# SCH_Hacker-Card_2024-10-03.net
KiCad netlist of a schematic drawn in EasyEDA
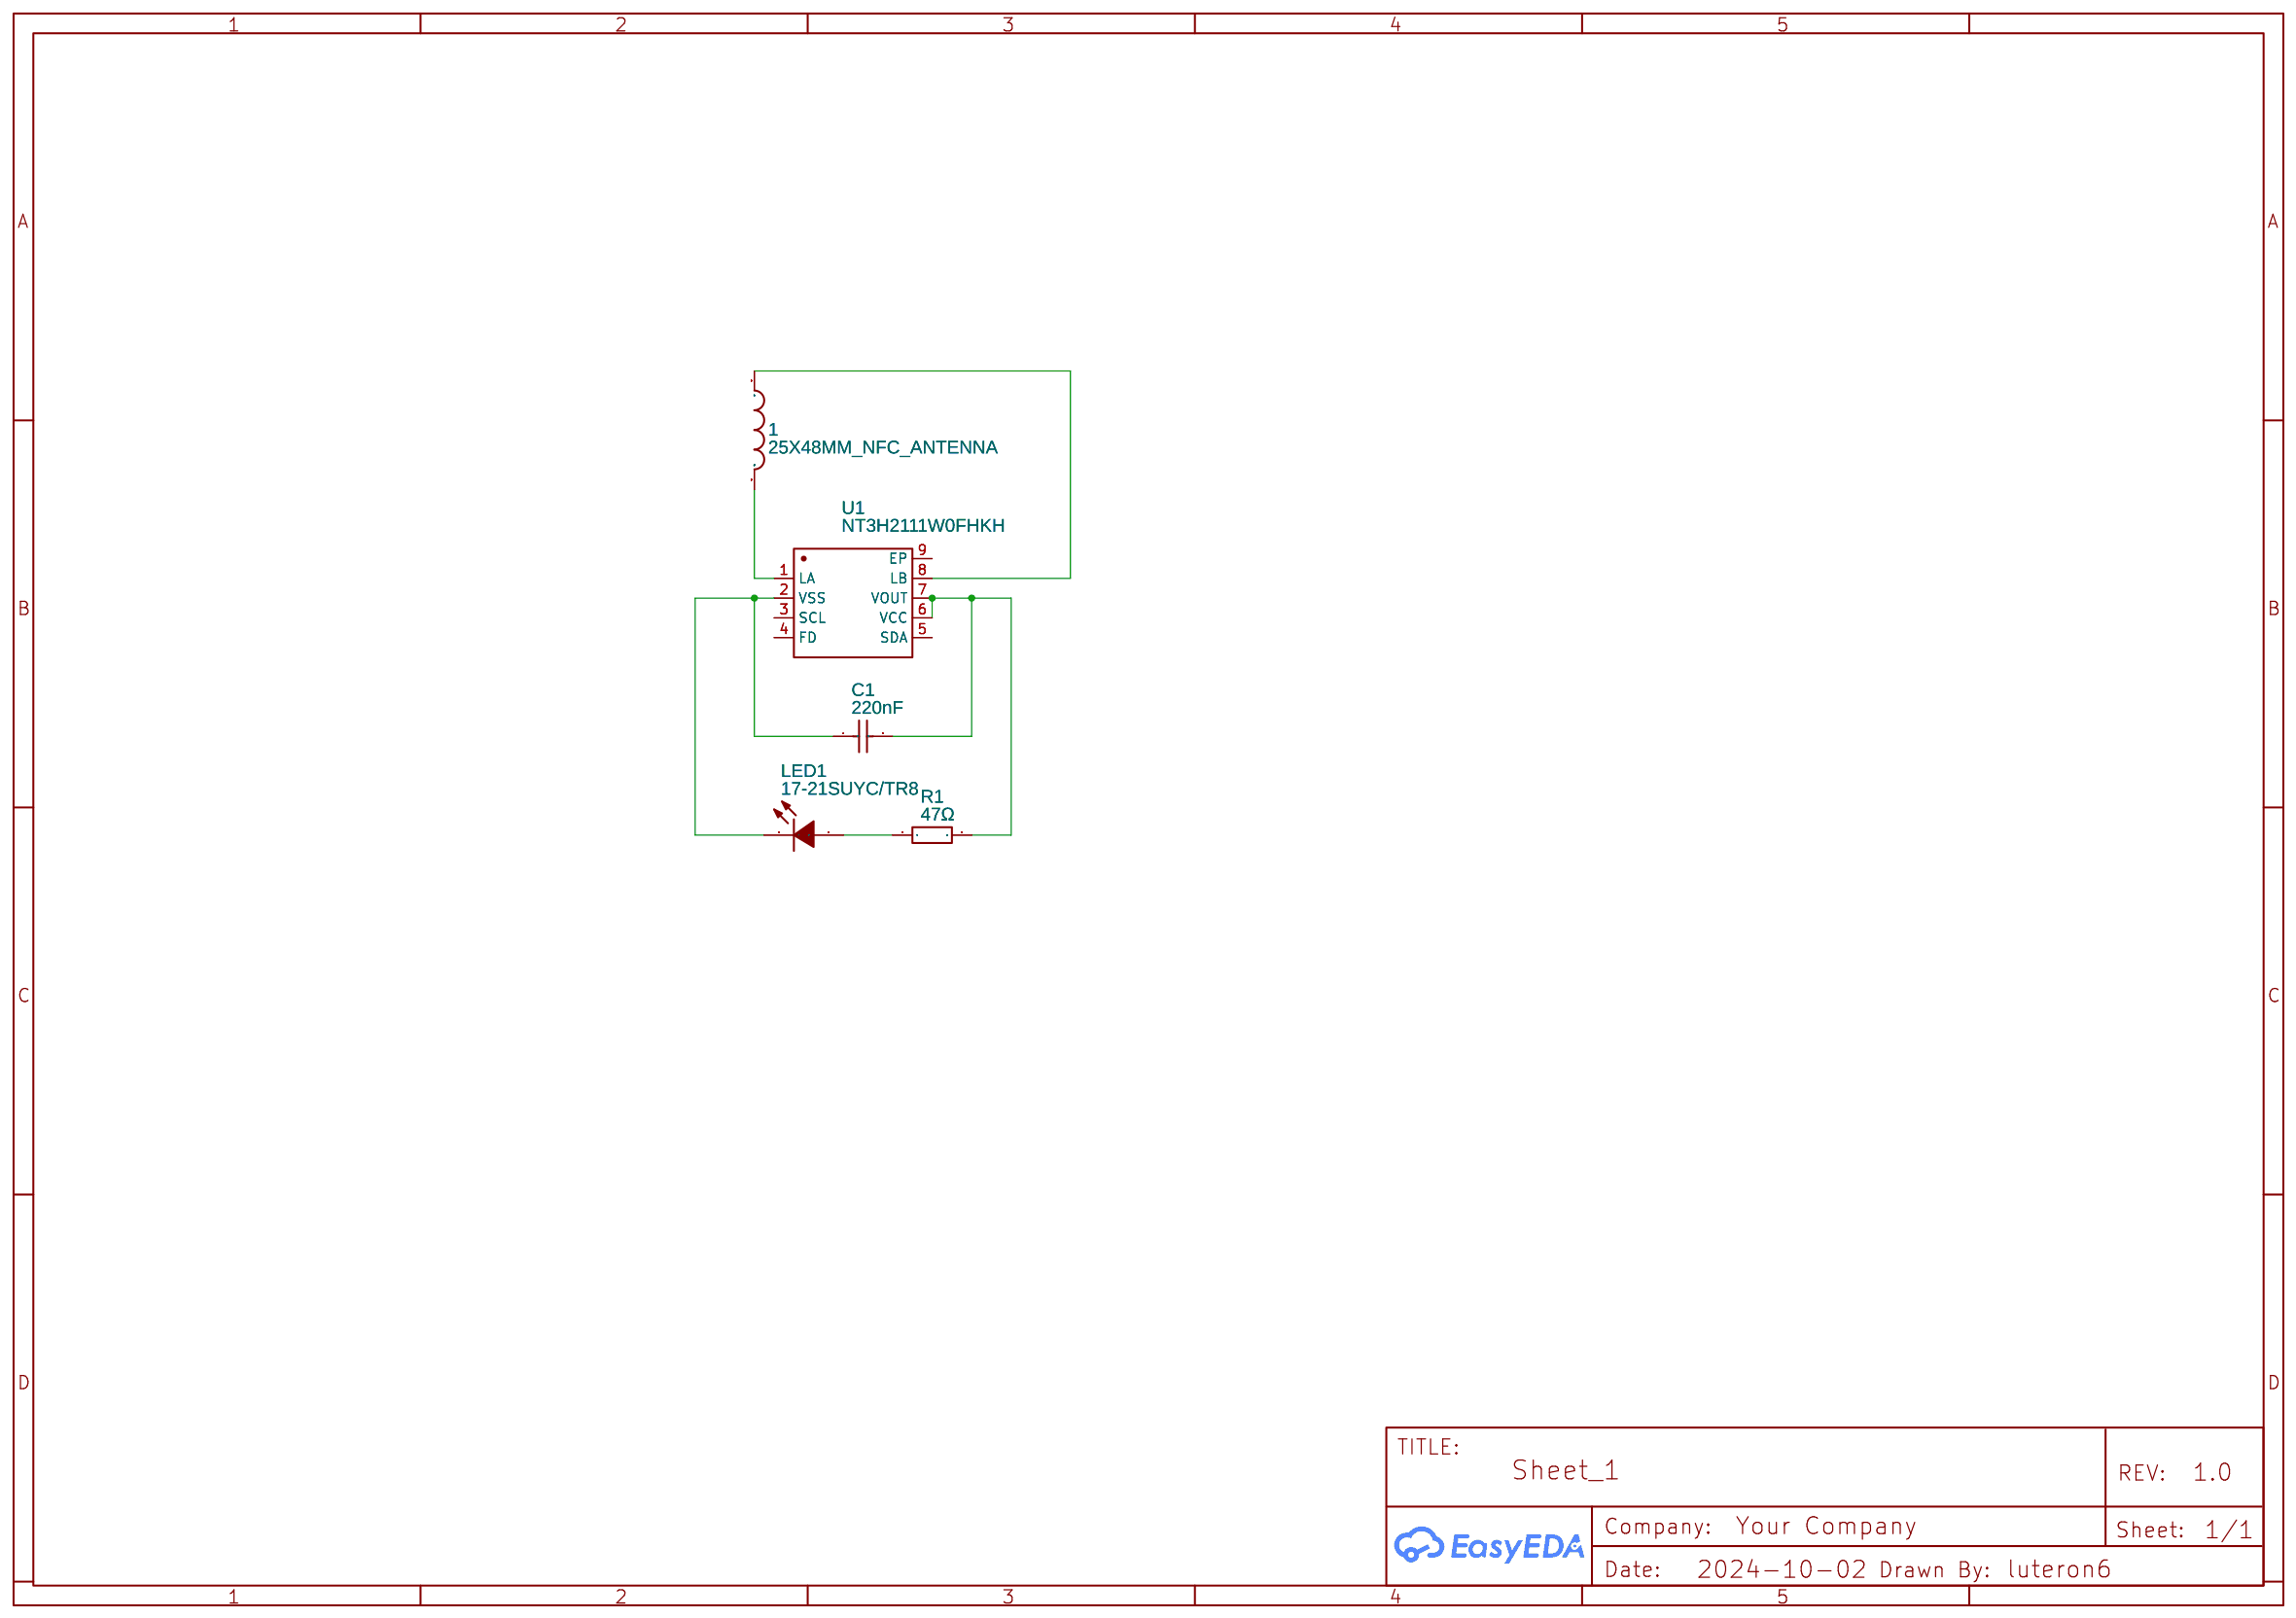
[diagram p0: schematic sheet]

(export (version "E")
  (design (tool "Eeschema 10.0.6"))
  (components
    (comp (ref "1") (value "25X48MM_NFC_ANTENNA") (libsource (lib "") (part "25X48MM_NFC_ANTENNA")))
    (comp (ref "C1")
      (value "220nF")
      (fields
        (field (name "Manufacturer Part") "CL10B224KA8NNNC")
        (field (name "Manufacturer") "SAMSUNG(三星)")
      )
      (libsource (lib "") (part "CL10B224KA8NNNC"))
    )
    (comp (ref "LED1")
      (value "17-21SUYC/TR8")
      (fields (field (name "Manufacturer Part") "KT-0805黄灯") (field (name "Manufacturer") "KENTO"))
      (libsource (lib "") (part "17-21SUYC/TR8"))
    )
    (comp (ref "R1")
      (value "47Ω")
      (fields
        (field (name "Manufacturer Part") "0603WAF470JT5E")
        (field (name "Manufacturer") "UNI-ROYAL(厚声)")
      )
      (libsource (lib "") (part "0603WAF470JT5E"))
    )
    (comp (ref "U1")
      (value "NT3H2111W0FHKH")
      (fields (field (name "Manufacturer") "NXP(恩智浦)"))
      (libsource (lib "") (part "NT3H2111W0FHKH"))
    )
  )
  (nets
    (net (code "1") (name "Net-(LED1-+)") (class "Default")
      (node (ref "LED1") (pin "1") (pinfunction "+_1") (pintype "unspecified"))
      (node (ref "R1") (pin "1") (pinfunction "1_1") (pintype "input"))
    )
    (net (code "2") (name "Net-(LED1--)") (class "Default")
      (node (ref "C1") (pin "1") (pinfunction "1_1") (pintype "input"))
      (node (ref "LED1") (pin "2") (pinfunction "-_2") (pintype "unspecified"))
      (node (ref "U1") (pin "2") (pinfunction "VSS_2") (pintype "unspecified"))
    )
    (net (code "3") (name "Net-(U1-LA)") (class "Default")
      (node (ref "1") (pin "P$2") (pinfunction "P$2_P$2") (pintype "bidirectional"))
      (node (ref "U1") (pin "1") (pinfunction "LA_1") (pintype "unspecified"))
    )
    (net (code "4") (name "Net-(U1-LB)") (class "Default")
      (node (ref "1") (pin "P$1") (pinfunction "P$1_P$1") (pintype "bidirectional"))
      (node (ref "U1") (pin "8") (pinfunction "LB_8") (pintype "unspecified"))
    )
    (net (code "5") (name "Net-(U1-VCC)") (class "Default")
      (node (ref "C1") (pin "2") (pinfunction "2_2") (pintype "input"))
      (node (ref "R1") (pin "2") (pinfunction "2_2") (pintype "input"))
      (node (ref "U1") (pin "6") (pinfunction "VCC_6") (pintype "unspecified"))
      (node (ref "U1") (pin "7") (pinfunction "VOUT_7") (pintype "unspecified"))
    )
    (net (code "6") (name "unconnected-(U1-EP-Pad9)") (class "Default")
      (node (ref "U1") (pin "9") (pinfunction "EP_9") (pintype "unspecified"))
    )
    (net (code "7") (name "unconnected-(U1-FD-Pad4)") (class "Default")
      (node (ref "U1") (pin "4") (pinfunction "FD_4") (pintype "unspecified"))
    )
    (net (code "8") (name "unconnected-(U1-SCL-Pad3)") (class "Default")
      (node (ref "U1") (pin "3") (pinfunction "SCL_3") (pintype "unspecified"))
    )
    (net (code "9") (name "unconnected-(U1-SDA-Pad5)") (class "Default")
      (node (ref "U1") (pin "5") (pinfunction "SDA_5") (pintype "unspecified"))
    )
  )
)
